# USB_interface.net
KiCad netlist of a schematic drawn in Altium Designer
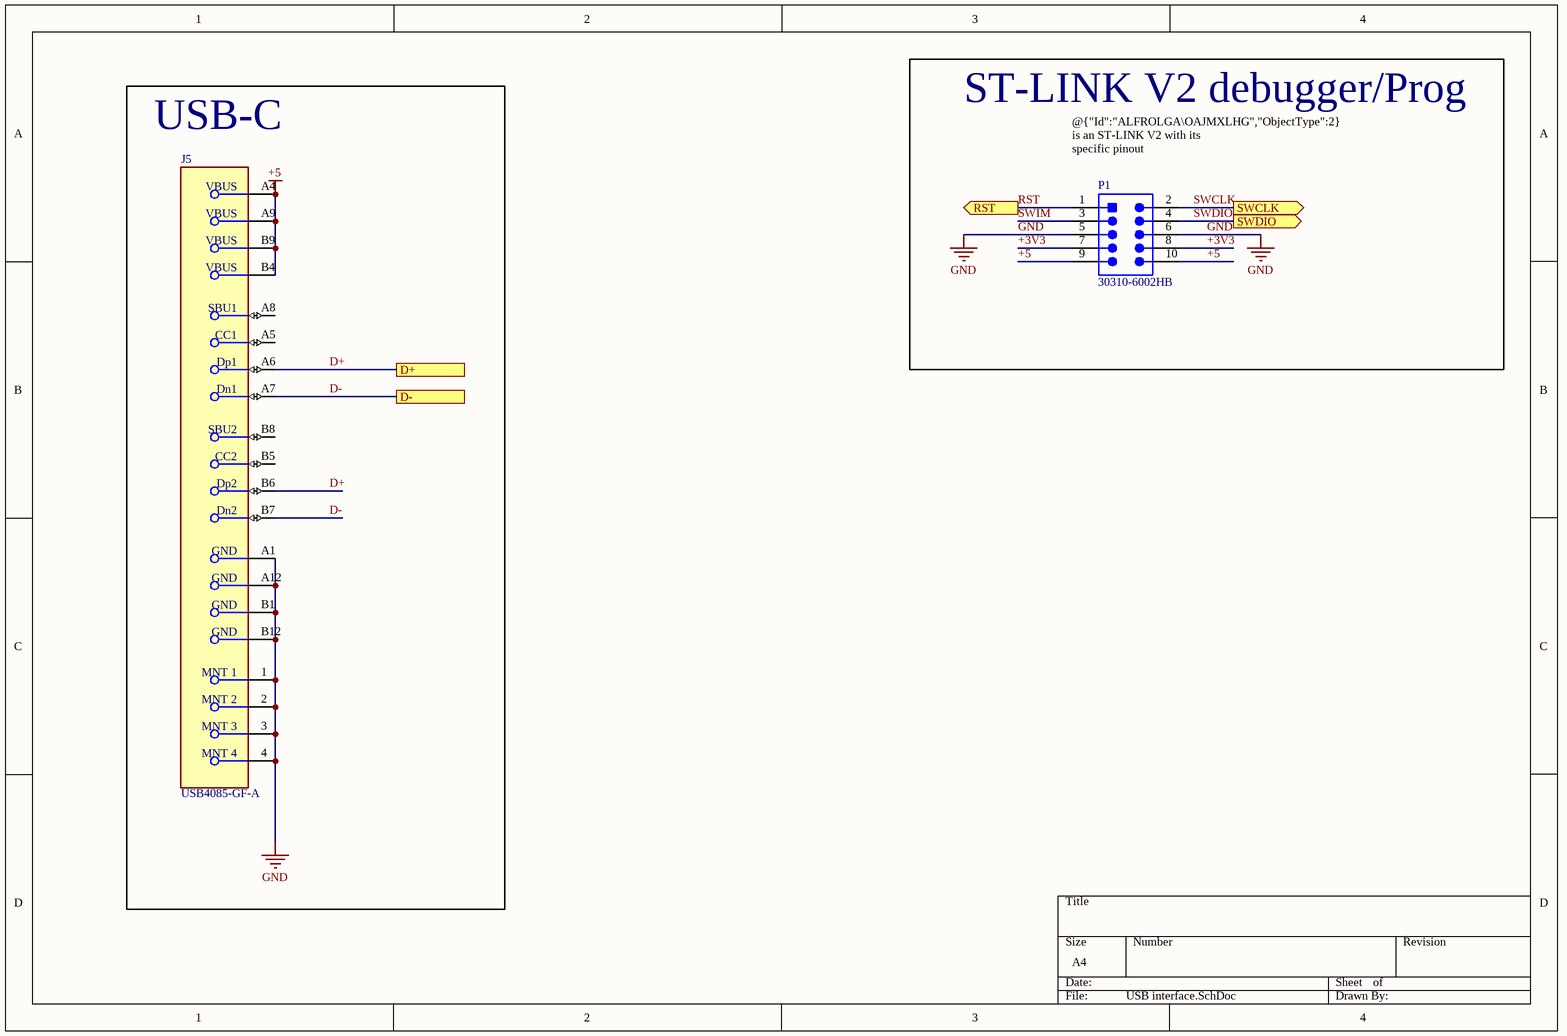
[diagram p0: USB interface.SchDoc]

(export (version "E")
  (design (tool "Eeschema 10.0.6"))
  (components
    (comp (ref "J5")
      (value "USB4085-GF-A")
      (footprint "FP-USB4085-GF-A-MFG")
      (description "CONN RCPT USB2.0 TYPE C 24POS RA")
      (libsource (lib "Altium Content Vault") (part "10fa745527c8b974685cbca3c197132"))
    )
    (comp (ref "P1")
      (value "30310-6002HB")
      (footprint "3M-30310-6002HB-10_V")
      (fields (field (name "MANUFACTURER") "3M"))
      (libsource (lib "Altium Content Vault") (part "CN-2P-M-R10"))
    )
  )
  (nets
    (net (code "1") (name "+5") (class "Default")
      (node (ref "J5") (pin "A4") (pinfunction "VBUS_A4") (pintype "power_in"))
      (node (ref "J5") (pin "A9") (pinfunction "VBUS_A9") (pintype "power_in"))
      (node (ref "J5") (pin "B4") (pinfunction "VBUS_B4") (pintype "power_in"))
      (node (ref "J5") (pin "B9") (pinfunction "VBUS_B9") (pintype "power_in"))
      (node (ref "P1") (pin "10") (pinfunction "10_10") (pintype "passive"))
      (node (ref "P1") (pin "9") (pinfunction "9_9") (pintype "passive"))
    )
    (net (code "2") (name "/+3V3") (class "Default")
      (node (ref "P1") (pin "7") (pinfunction "7_7") (pintype "passive"))
      (node (ref "P1") (pin "8") (pinfunction "8_8") (pintype "passive"))
    )
    (net (code "3") (name "/D+") (class "Default")
      (node (ref "J5") (pin "A6") (pinfunction "Dp1_A6") (pintype "bidirectional"))
      (node (ref "J5") (pin "B6") (pinfunction "Dp2_B6") (pintype "bidirectional"))
    )
    (net (code "4") (name "/D-") (class "Default")
      (node (ref "J5") (pin "A7") (pinfunction "Dn1_A7") (pintype "bidirectional"))
      (node (ref "J5") (pin "B7") (pinfunction "Dn2_B7") (pintype "bidirectional"))
    )
    (net (code "5") (name "/RST") (class "Default")
      (node (ref "P1") (pin "1") (pinfunction "1_1") (pintype "passive"))
    )
    (net (code "6") (name "/SWCLK") (class "Default")
      (node (ref "P1") (pin "2") (pinfunction "2_2") (pintype "passive"))
    )
    (net (code "7") (name "/SWDIO") (class "Default")
      (node (ref "P1") (pin "4") (pinfunction "4_4") (pintype "passive"))
    )
    (net (code "8") (name "/SWIM") (class "Default")
      (node (ref "P1") (pin "3") (pinfunction "3_3") (pintype "passive"))
    )
    (net (code "9") (name "GND") (class "Default")
      (node (ref "J5") (pin "1") (pinfunction "MNT_1_1") (pintype "passive"))
      (node (ref "J5") (pin "2") (pinfunction "MNT_2_2") (pintype "passive"))
      (node (ref "J5") (pin "3") (pinfunction "MNT_3_3") (pintype "passive"))
      (node (ref "J5") (pin "4") (pinfunction "MNT_4_4") (pintype "passive"))
      (node (ref "J5") (pin "A1") (pinfunction "GND_A1") (pintype "power_in"))
      (node (ref "J5") (pin "A12") (pinfunction "GND_A12") (pintype "power_in"))
      (node (ref "J5") (pin "B1") (pinfunction "GND_B1") (pintype "power_in"))
      (node (ref "J5") (pin "B12") (pinfunction "GND_B12") (pintype "power_in"))
      (node (ref "P1") (pin "5") (pinfunction "5_5") (pintype "passive"))
      (node (ref "P1") (pin "6") (pinfunction "6_6") (pintype "passive"))
    )
    (net (code "10") (name "unconnected-(J5-CC1-PadA5)") (class "Default")
      (node (ref "J5") (pin "A5") (pinfunction "CC1_A5") (pintype "bidirectional"))
    )
    (net (code "11") (name "unconnected-(J5-CC2-PadB5)") (class "Default")
      (node (ref "J5") (pin "B5") (pinfunction "CC2_B5") (pintype "bidirectional"))
    )
    (net (code "12") (name "unconnected-(J5-SBU1-PadA8)") (class "Default")
      (node (ref "J5") (pin "A8") (pinfunction "SBU1_A8") (pintype "bidirectional"))
    )
    (net (code "13") (name "unconnected-(J5-SBU2-PadB8)") (class "Default")
      (node (ref "J5") (pin "B8") (pinfunction "SBU2_B8") (pintype "bidirectional"))
    )
  )
)
